# phase_compare.net
KiCad netlist of a schematic drawn in Altium Designer
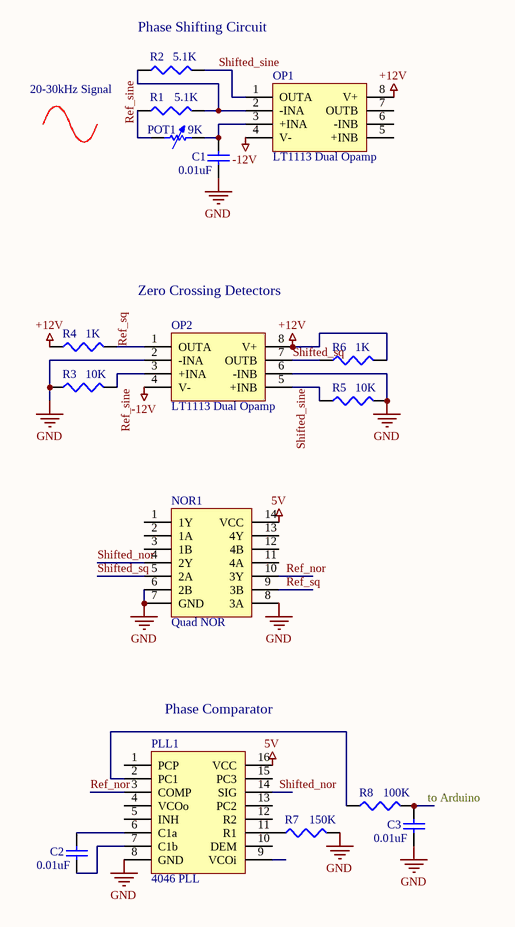
[diagram p0: phase_compare.SchDoc]

(export (version "E")
  (design (tool "Eeschema 10.0.6"))
  (components
    (comp (ref "C1")
      (value "0.01uF")
      (footprint "C1206")
      (description "Capacitor (Semiconductor SIM Model)")
      (fields (field (name "Comment") "Cap Semi") (field (name "PUBLISHER") "Altium Limited"))
      (libsource (lib "Miscellaneous Devices") (part "Cap Semi"))
    )
    (comp (ref "C2")
      (value "0.01uF")
      (footprint "C1206")
      (description "Capacitor (Semiconductor SIM Model)")
      (fields (field (name "Comment") "Cap Semi") (field (name "PUBLISHER") "Altium Limited"))
      (libsource (lib "Miscellaneous Devices") (part "Cap Semi"))
    )
    (comp (ref "C3")
      (value "0.01uF")
      (footprint "C1206")
      (description "Capacitor (Semiconductor SIM Model)")
      (fields (field (name "Comment") "Cap Semi") (field (name "PUBLISHER") "Altium Limited"))
      (libsource (lib "Miscellaneous Devices") (part "Cap Semi"))
    )
    (comp (ref "NOR1")
      (value "Quad NOR")
      (description "HD74HC02")
      (libsource (lib "sonar_rev2") (part "Quad NOR"))
    )
    (comp (ref "OP1") (value "LT1113 Dual Opamp") (libsource (lib "Schlib1") (part "LT1113 OPAMP")))
    (comp (ref "OP2") (value "LT1113 Dual Opamp") (libsource (lib "Schlib1") (part "LT1113 OPAMP")))
    (comp (ref "PLL1")
      (value "4046 PLL")
      (footprint "sonar_rev2:4046PLL")
      (description "CD74HC4046A")
      (libsource (lib "sonar_rev2") (part "4046 PLL"))
    )
    (comp (ref "POT1")
      (value "9K")
      (footprint "AXIAL-0.7")
      (description "Variable Resistor")
      (fields (field (name "Comment") "Res Adj1") (field (name "PUBLISHER") "Altium Limited"))
      (libsource (lib "Miscellaneous Devices") (part "Res Adj1"))
    )
    (comp (ref "R1")
      (value "5.1K")
      (footprint "J1-0603")
      (description "Resistor")
      (fields (field (name "Comment") "Res3") (field (name "PUBLISHER") "Altium Limited"))
      (libsource (lib "Miscellaneous Devices") (part "Res3"))
    )
    (comp (ref "R2")
      (value "5.1K")
      (footprint "J1-0603")
      (description "Resistor")
      (fields (field (name "Comment") "Res3") (field (name "PUBLISHER") "Altium Limited"))
      (libsource (lib "Miscellaneous Devices") (part "Res3"))
    )
    (comp (ref "R3")
      (value "10K")
      (footprint "J1-0603")
      (description "Resistor")
      (fields (field (name "Comment") "Res3") (field (name "PUBLISHER") "Altium Limited"))
      (libsource (lib "Miscellaneous Devices") (part "Res3"))
    )
    (comp (ref "R4")
      (value "1K")
      (footprint "J1-0603")
      (description "Resistor")
      (fields (field (name "Comment") "Res3") (field (name "PUBLISHER") "Altium Limited"))
      (libsource (lib "Miscellaneous Devices") (part "Res3"))
    )
    (comp (ref "R5")
      (value "10K")
      (footprint "J1-0603")
      (description "Resistor")
      (fields (field (name "Comment") "Res3") (field (name "PUBLISHER") "Altium Limited"))
      (libsource (lib "Miscellaneous Devices") (part "Res3"))
    )
    (comp (ref "R6")
      (value "1K")
      (footprint "J1-0603")
      (description "Resistor")
      (fields (field (name "Comment") "Res3") (field (name "PUBLISHER") "Altium Limited"))
      (libsource (lib "Miscellaneous Devices") (part "Res3"))
    )
    (comp (ref "R7")
      (value "150K")
      (footprint "J1-0603")
      (description "Resistor")
      (fields (field (name "Comment") "Res3") (field (name "PUBLISHER") "Altium Limited"))
      (libsource (lib "Miscellaneous Devices") (part "Res3"))
    )
    (comp (ref "R8")
      (value "100K")
      (footprint "J1-0603")
      (description "Resistor")
      (fields (field (name "Comment") "Res3") (field (name "PUBLISHER") "Altium Limited"))
      (libsource (lib "Miscellaneous Devices") (part "Res3"))
    )
  )
  (nets
    (net (code "1") (name "+12V") (class "Default")
      (node (ref "OP1") (pin "8") (pinfunction "V+_8") (pintype "power_in"))
      (node (ref "OP2") (pin "8") (pinfunction "V+_8") (pintype "power_in"))
      (node (ref "R4") (pin "1") (pinfunction "1_1") (pintype "passive"))
      (node (ref "R6") (pin "2") (pinfunction "2_2") (pintype "passive"))
    )
    (net (code "2") (name "-12V") (class "Default")
      (node (ref "OP1") (pin "4") (pinfunction "V-_4") (pintype "power_in"))
      (node (ref "OP2") (pin "4") (pinfunction "V-_4") (pintype "power_in"))
    )
    (net (code "3") (name "/Ref_nor") (class "Default")
      (node (ref "NOR1") (pin "10") (pinfunction "3Y_10") (pintype "power_in"))
      (node (ref "PLL1") (pin "3") (pinfunction "COMP_3") (pintype "power_in"))
    )
    (net (code "4") (name "/Ref_sine") (class "Default")
      (node (ref "OP2") (pin "3") (pinfunction "+INA_3") (pintype "power_in"))
      (node (ref "POT1") (pin "1") (pinfunction "1_1") (pintype "passive"))
      (node (ref "R1") (pin "1") (pinfunction "1_1") (pintype "passive"))
      (node (ref "R3") (pin "2") (pinfunction "2_2") (pintype "passive"))
    )
    (net (code "5") (name "/Ref_sq") (class "Default")
      (node (ref "NOR1") (pin "9") (pinfunction "3B_9") (pintype "power_in"))
      (node (ref "OP2") (pin "1") (pinfunction "OUTA_1") (pintype "power_in"))
      (node (ref "R4") (pin "2") (pinfunction "2_2") (pintype "passive"))
    )
    (net (code "6") (name "/Shifted_nor") (class "Default")
      (node (ref "NOR1") (pin "4") (pinfunction "2Y_4") (pintype "power_in"))
      (node (ref "PLL1") (pin "14") (pinfunction "SIG_14") (pintype "power_in"))
    )
    (net (code "7") (name "/Shifted_sine") (class "Default")
      (node (ref "OP1") (pin "1") (pinfunction "OUTA_1") (pintype "power_in"))
      (node (ref "OP2") (pin "5") (pinfunction "+INB_5") (pintype "power_in"))
      (node (ref "R2") (pin "2") (pinfunction "2_2") (pintype "passive"))
      (node (ref "R5") (pin "1") (pinfunction "1_1") (pintype "passive"))
    )
    (net (code "8") (name "/Shifted_sq") (class "Default")
      (node (ref "NOR1") (pin "5") (pinfunction "2A_5") (pintype "power_in"))
      (node (ref "OP2") (pin "7") (pinfunction "OUTB_7") (pintype "power_in"))
      (node (ref "R6") (pin "1") (pinfunction "1_1") (pintype "passive"))
    )
    (net (code "9") (name "5V") (class "Default")
      (node (ref "NOR1") (pin "14") (pinfunction "VCC_14") (pintype "power_in"))
      (node (ref "PLL1") (pin "16") (pinfunction "VCC_16") (pintype "power_in"))
    )
    (net (code "10") (name "GND") (class "Default")
      (node (ref "C1") (pin "1") (pinfunction "1_1") (pintype "passive"))
      (node (ref "C3") (pin "1") (pinfunction "1_1") (pintype "passive"))
      (node (ref "NOR1") (pin "6") (pinfunction "2B_6") (pintype "power_in"))
      (node (ref "NOR1") (pin "7") (pinfunction "GND_7") (pintype "power_in"))
      (node (ref "NOR1") (pin "8") (pinfunction "3A_8") (pintype "power_in"))
      (node (ref "OP2") (pin "2") (pinfunction "-INA_2") (pintype "power_in"))
      (node (ref "OP2") (pin "6") (pinfunction "-INB_6") (pintype "power_in"))
      (node (ref "PLL1") (pin "8") (pinfunction "GND_8") (pintype "power_in"))
      (node (ref "R3") (pin "1") (pinfunction "1_1") (pintype "passive"))
      (node (ref "R5") (pin "2") (pinfunction "2_2") (pintype "passive"))
      (node (ref "R7") (pin "2") (pinfunction "2_2") (pintype "passive"))
    )
    (net (code "11") (name "Net-(C3-Pad2)") (class "Default")
      (node (ref "C3") (pin "2") (pinfunction "2_2") (pintype "passive"))
      (node (ref "R8") (pin "2") (pinfunction "2_2") (pintype "passive"))
    )
    (net (code "12") (name "Net-(OP1-+INA)") (class "Default")
      (node (ref "C1") (pin "2") (pinfunction "2_2") (pintype "passive"))
      (node (ref "OP1") (pin "3") (pinfunction "+INA_3") (pintype "power_in"))
      (node (ref "POT1") (pin "2") (pinfunction "2_2") (pintype "passive"))
    )
    (net (code "13") (name "Net-(OP1--INA)") (class "Default")
      (node (ref "OP1") (pin "2") (pinfunction "-INA_2") (pintype "power_in"))
      (node (ref "R1") (pin "2") (pinfunction "2_2") (pintype "passive"))
      (node (ref "R2") (pin "1") (pinfunction "1_1") (pintype "passive"))
    )
    (net (code "14") (name "Net-(PLL1-C1a)") (class "Default")
      (node (ref "C2") (pin "2") (pinfunction "2_2") (pintype "passive"))
      (node (ref "PLL1") (pin "6") (pinfunction "C1a_6") (pintype "power_in"))
    )
    (net (code "15") (name "Net-(PLL1-C1b)") (class "Default")
      (node (ref "C2") (pin "1") (pinfunction "1_1") (pintype "passive"))
      (node (ref "PLL1") (pin "7") (pinfunction "C1b_7") (pintype "power_in"))
    )
    (net (code "16") (name "Net-(PLL1-PC1)") (class "Default")
      (node (ref "PLL1") (pin "2") (pinfunction "PC1_2") (pintype "power_in"))
      (node (ref "R8") (pin "1") (pinfunction "1_1") (pintype "passive"))
    )
    (net (code "17") (name "Net-(PLL1-R1)") (class "Default")
      (node (ref "PLL1") (pin "11") (pinfunction "R1_11") (pintype "power_in"))
      (node (ref "R7") (pin "1") (pinfunction "1_1") (pintype "passive"))
    )
    (net (code "18") (name "unconnected-(NOR1-1A-Pad2)") (class "Default")
      (node (ref "NOR1") (pin "2") (pinfunction "1A_2") (pintype "power_in"))
    )
    (net (code "19") (name "unconnected-(NOR1-1B-Pad3)") (class "Default")
      (node (ref "NOR1") (pin "3") (pinfunction "1B_3") (pintype "power_in"))
    )
    (net (code "20") (name "unconnected-(NOR1-1Y-Pad1)") (class "Default")
      (node (ref "NOR1") (pin "1") (pinfunction "1Y_1") (pintype "power_in"))
    )
    (net (code "21") (name "unconnected-(NOR1-4A-Pad11)") (class "Default")
      (node (ref "NOR1") (pin "11") (pinfunction "4A_11") (pintype "power_in"))
    )
    (net (code "22") (name "unconnected-(NOR1-4B-Pad12)") (class "Default")
      (node (ref "NOR1") (pin "12") (pinfunction "4B_12") (pintype "power_in"))
    )
    (net (code "23") (name "unconnected-(NOR1-4Y-Pad13)") (class "Default")
      (node (ref "NOR1") (pin "13") (pinfunction "4Y_13") (pintype "power_in"))
    )
    (net (code "24") (name "unconnected-(OP1-+INB-Pad5)") (class "Default")
      (node (ref "OP1") (pin "5") (pinfunction "+INB_5") (pintype "power_in"))
    )
    (net (code "25") (name "unconnected-(OP1--INB-Pad6)") (class "Default")
      (node (ref "OP1") (pin "6") (pinfunction "-INB_6") (pintype "power_in"))
    )
    (net (code "26") (name "unconnected-(OP1-OUTB-Pad7)") (class "Default")
      (node (ref "OP1") (pin "7") (pinfunction "OUTB_7") (pintype "power_in"))
    )
    (net (code "27") (name "unconnected-(PLL1-DEM-Pad10)") (class "Default")
      (node (ref "PLL1") (pin "10") (pinfunction "DEM_10") (pintype "power_in"))
    )
    (net (code "28") (name "unconnected-(PLL1-INH-Pad5)") (class "Default")
      (node (ref "PLL1") (pin "5") (pinfunction "INH_5") (pintype "power_in"))
    )
    (net (code "29") (name "unconnected-(PLL1-PC2-Pad13)") (class "Default")
      (node (ref "PLL1") (pin "13") (pinfunction "PC2_13") (pintype "power_in"))
    )
    (net (code "30") (name "unconnected-(PLL1-PC3-Pad15)") (class "Default")
      (node (ref "PLL1") (pin "15") (pinfunction "PC3_15") (pintype "power_in"))
    )
    (net (code "31") (name "unconnected-(PLL1-PCP-Pad1)") (class "Default")
      (node (ref "PLL1") (pin "1") (pinfunction "PCP_1") (pintype "power_in"))
    )
    (net (code "32") (name "unconnected-(PLL1-R2-Pad12)") (class "Default")
      (node (ref "PLL1") (pin "12") (pinfunction "R2_12") (pintype "power_in"))
    )
    (net (code "33") (name "unconnected-(PLL1-VCOi-Pad9)") (class "Default")
      (node (ref "PLL1") (pin "9") (pinfunction "VCOi_9") (pintype "power_in"))
    )
    (net (code "34") (name "unconnected-(PLL1-VCOo-Pad4)") (class "Default")
      (node (ref "PLL1") (pin "4") (pinfunction "VCOo_4") (pintype "power_in"))
    )
  )
)
